# mechanics.net
KiCad netlist of a schematic drawn in Altium Designer
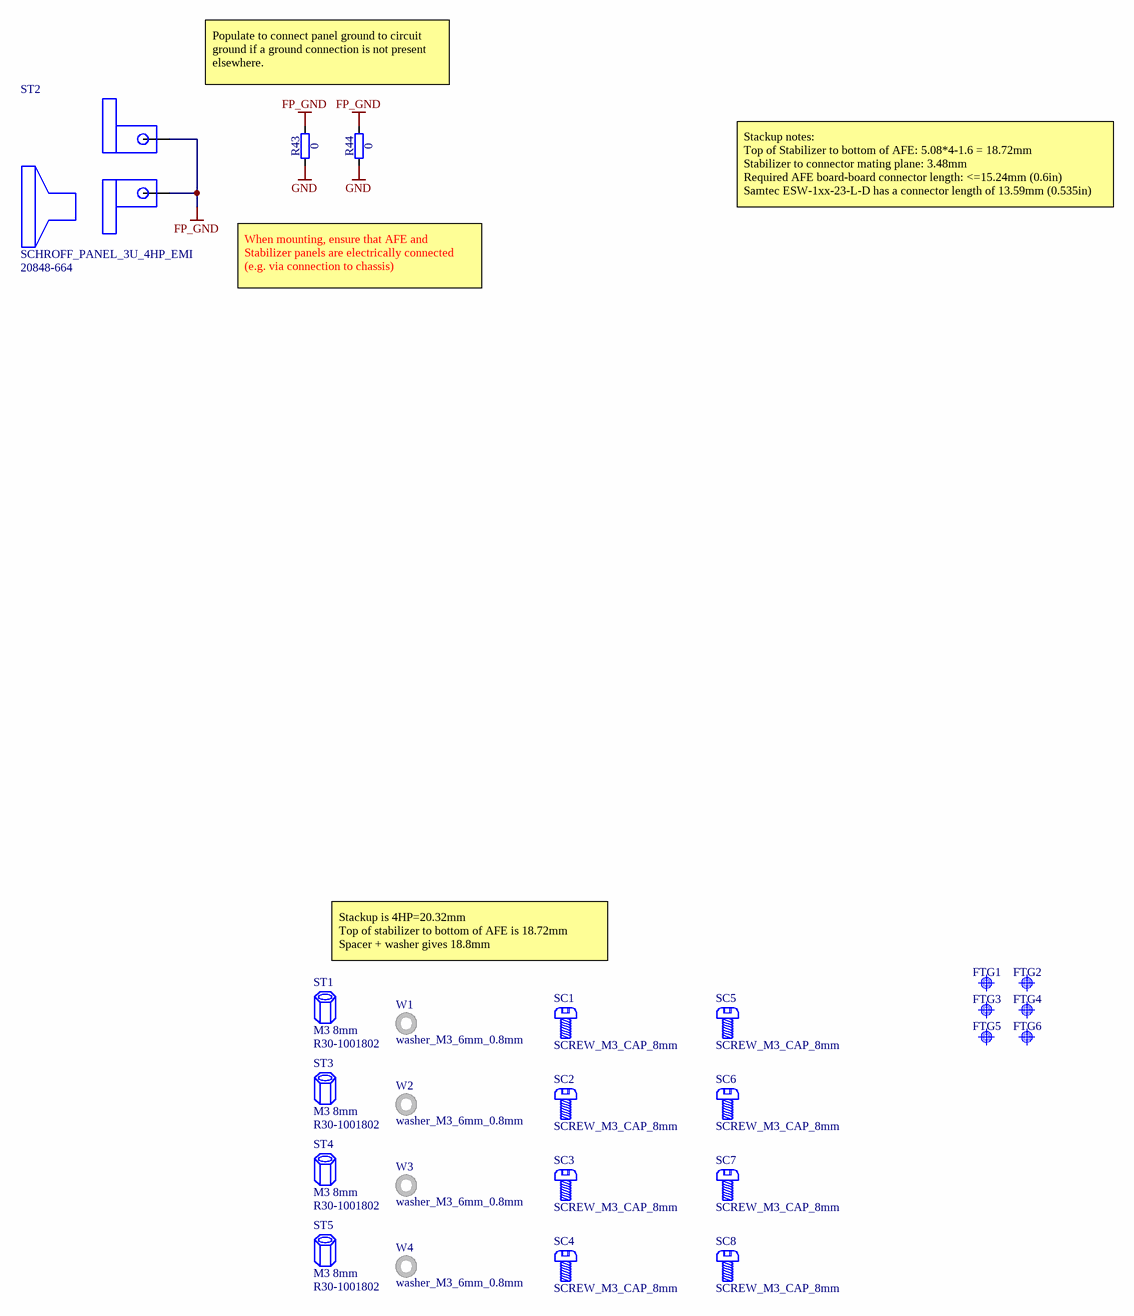
[diagram p0: mechanics.SchDoc]

(export (version "E")
  (design (tool "Eeschema 10.0.6"))
  (components
    (comp (ref "FTG1")
      (value "Use only in PCB")
      (footprint "FIDUCIAL_TOP_C100-200")
      (description "Fiducial Target")
      (fields (field (name "PART NUMBER") "FIDUCIAL_TARGET_C100-200") (field (name "AUTHOR") "CERN DEM JLC"))
      (libsource (lib "Eletro-mechanical") (part "Fiducial Target"))
    )
    (comp (ref "FTG2")
      (value "Use only in PCB")
      (footprint "FIDUCIAL_TOP_C100-200")
      (description "Fiducial Target")
      (fields (field (name "PART NUMBER") "FIDUCIAL_TARGET_C100-200") (field (name "AUTHOR") "CERN DEM JLC"))
      (libsource (lib "Eletro-mechanical") (part "Fiducial Target"))
    )
    (comp (ref "FTG3")
      (value "Use only in PCB")
      (footprint "FIDUCIAL_TOP_C100-200")
      (description "Fiducial Target")
      (fields (field (name "PART NUMBER") "FIDUCIAL_TARGET_C100-200") (field (name "AUTHOR") "CERN DEM JLC"))
      (libsource (lib "Eletro-mechanical") (part "Fiducial Target"))
    )
    (comp (ref "FTG4")
      (value "Use only in PCB")
      (footprint "FIDUCIAL_TOP_C100-200")
      (description "Fiducial Target")
      (fields (field (name "PART NUMBER") "FIDUCIAL_TARGET_C100-200") (field (name "AUTHOR") "CERN DEM JLC"))
      (libsource (lib "Eletro-mechanical") (part "Fiducial Target"))
    )
    (comp (ref "FTG5")
      (value "Use only in PCB")
      (footprint "FIDUCIAL_TOP_C100-200")
      (description "Fiducial Target")
      (fields (field (name "PART NUMBER") "FIDUCIAL_TARGET_C100-200") (field (name "AUTHOR") "CERN DEM JLC"))
      (libsource (lib "Eletro-mechanical") (part "Fiducial Target"))
    )
    (comp (ref "FTG6")
      (value "Use only in PCB")
      (footprint "FIDUCIAL_TOP_C100-200")
      (description "Fiducial Target")
      (fields (field (name "PART NUMBER") "FIDUCIAL_TARGET_C100-200") (field (name "AUTHOR") "CERN DEM JLC"))
      (libsource (lib "Eletro-mechanical") (part "Fiducial Target"))
    )
    (comp (ref "R43")
      (value "0")
      (footprint "RESC1608X55N")
      (description "Resistor")
      (fields
        (field (name "PART NUMBER") "R0603_0R_JUMPER")
        (field (name "MANUFACTURER") "GENERIC")
        (field (name "AUTHOR") "CERN DEM JLC")
      )
      (libsource (lib "Resistors") (part "Resistor"))
    )
    (comp (ref "R44")
      (value "0")
      (footprint "RESC1608X55N")
      (description "Resistor")
      (fields
        (field (name "PART NUMBER") "R0603_0R_JUMPER")
        (field (name "MANUFACTURER") "GENERIC")
        (field (name "AUTHOR") "CERN DEM JLC")
      )
      (libsource (lib "Resistors") (part "Resistor"))
    )
    (comp (ref "SC1")
      (value "SCREW_M3_CAP_8mm")
      (footprint "mechanical:SCREW_M3_CAP_8mm")
      (description "M3 x 8mm cap head screw")
      (fields
        (field (name "MANUFACTURER") "Accu Limited")
        (field (name "MANUFACTURER PART NUMBER") "SSCF-M3-8-12.9-Z")
      )
      (libsource (lib "mechanical") (part "SCREW_M3_CAP_8mm"))
    )
    (comp (ref "SC2")
      (value "SCREW_M3_CAP_8mm")
      (footprint "mechanical:SCREW_M3_CAP_8mm")
      (description "M3 x 8mm cap head screw")
      (fields
        (field (name "MANUFACTURER") "Accu Limited")
        (field (name "MANUFACTURER PART NUMBER") "SSCF-M3-8-12.9-Z")
      )
      (libsource (lib "mechanical") (part "SCREW_M3_CAP_8mm"))
    )
    (comp (ref "SC3")
      (value "SCREW_M3_CAP_8mm")
      (footprint "mechanical:SCREW_M3_CAP_8mm")
      (description "M3 x 8mm cap head screw")
      (fields
        (field (name "MANUFACTURER") "Accu Limited")
        (field (name "MANUFACTURER PART NUMBER") "SSCF-M3-8-12.9-Z")
      )
      (libsource (lib "mechanical") (part "SCREW_M3_CAP_8mm"))
    )
    (comp (ref "SC4")
      (value "SCREW_M3_CAP_8mm")
      (footprint "mechanical:SCREW_M3_CAP_8mm")
      (description "M3 x 8mm cap head screw")
      (fields
        (field (name "MANUFACTURER") "Accu Limited")
        (field (name "MANUFACTURER PART NUMBER") "SSCF-M3-8-12.9-Z")
      )
      (libsource (lib "mechanical") (part "SCREW_M3_CAP_8mm"))
    )
    (comp (ref "SC5")
      (value "SCREW_M3_CAP_8mm")
      (footprint "mechanical:SCREW_M3_CAP_8mm")
      (description "M3 x 8mm cap head screw")
      (fields
        (field (name "MANUFACTURER") "Accu Limited")
        (field (name "MANUFACTURER PART NUMBER") "SSCF-M3-8-12.9-Z")
      )
      (libsource (lib "mechanical") (part "SCREW_M3_CAP_8mm"))
    )
    (comp (ref "SC6")
      (value "SCREW_M3_CAP_8mm")
      (footprint "mechanical:SCREW_M3_CAP_8mm")
      (description "M3 x 8mm cap head screw")
      (fields
        (field (name "MANUFACTURER") "Accu Limited")
        (field (name "MANUFACTURER PART NUMBER") "SSCF-M3-8-12.9-Z")
      )
      (libsource (lib "mechanical") (part "SCREW_M3_CAP_8mm"))
    )
    (comp (ref "SC7")
      (value "SCREW_M3_CAP_8mm")
      (footprint "mechanical:SCREW_M3_CAP_8mm")
      (description "M3 x 8mm cap head screw")
      (fields
        (field (name "MANUFACTURER") "Accu Limited")
        (field (name "MANUFACTURER PART NUMBER") "SSCF-M3-8-12.9-Z")
      )
      (libsource (lib "mechanical") (part "SCREW_M3_CAP_8mm"))
    )
    (comp (ref "SC8")
      (value "SCREW_M3_CAP_8mm")
      (footprint "mechanical:SCREW_M3_CAP_8mm")
      (description "M3 x 8mm cap head screw")
      (fields
        (field (name "MANUFACTURER") "Accu Limited")
        (field (name "MANUFACTURER PART NUMBER") "SSCF-M3-8-12.9-Z")
      )
      (libsource (lib "mechanical") (part "SCREW_M3_CAP_8mm"))
    )
    (comp (ref "ST1")
      (value "M3 8mm")
      (footprint "mechanical:R30-1001802")
      (description "M3.0x18 standoff")
      (fields (field (name "MANUFACTURER") "Harwin") (field (name "MANUFACTURER PART NUMBER") "R30-1001802"))
      (libsource (lib "mechanical") (part "STANDOFF_HARWIN_R30_1001802"))
    )
    (comp (ref "ST2")
      (value "SCHROFF_PANEL_3U_4HP_EMI")
      (footprint "mechanical:SCHROFF_PANEL_3HP_4U")
      (description "Schroff 3HP 4U EUROCARD Panel with EMI gaskets kit")
      (fields (field (name "MANUFACTURER") "Schroff") (field (name "MANUFACTURER PART NUMBER") "20848-664"))
      (libsource (lib "mechanical") (part "SCHROFF_PANEL_3U_4HP_EMI"))
    )
    (comp (ref "ST3")
      (value "M3 8mm")
      (footprint "mechanical:R30-1001802")
      (description "M3.0x18 standoff")
      (fields (field (name "MANUFACTURER") "Harwin") (field (name "MANUFACTURER PART NUMBER") "R30-1001802"))
      (libsource (lib "mechanical") (part "STANDOFF_HARWIN_R30_1001802"))
    )
    (comp (ref "ST4")
      (value "M3 8mm")
      (footprint "mechanical:R30-1001802")
      (description "M3.0x18 standoff")
      (fields (field (name "MANUFACTURER") "Harwin") (field (name "MANUFACTURER PART NUMBER") "R30-1001802"))
      (libsource (lib "mechanical") (part "STANDOFF_HARWIN_R30_1001802"))
    )
    (comp (ref "ST5")
      (value "M3 8mm")
      (footprint "mechanical:R30-1001802")
      (description "M3.0x18 standoff")
      (fields (field (name "MANUFACTURER") "Harwin") (field (name "MANUFACTURER PART NUMBER") "R30-1001802"))
      (libsource (lib "mechanical") (part "STANDOFF_HARWIN_R30_1001802"))
    )
    (comp (ref "W1")
      (value "washer_M3_6mm_0.8mm")
      (footprint "mechanical:washer_M3_6mm_0.8mm")
      (description "M3 Washer:\r\nID: 3.2mm\r\nOD: 6mm\r\nThickness 0.8mm")
      (fields
        (field (name "MANUFACTURER") "Accu Limited")
        (field (name "MANUFACTURER PART NUMBER") "HAFZ-M3-A4")
      )
      (libsource (lib "mechanical") (part "washer_M3_6mm_0.8mm"))
    )
    (comp (ref "W2")
      (value "washer_M3_6mm_0.8mm")
      (footprint "mechanical:washer_M3_6mm_0.8mm")
      (description "M3 Washer:\r\nID: 3.2mm\r\nOD: 6mm\r\nThickness 0.8mm")
      (fields
        (field (name "MANUFACTURER") "Accu Limited")
        (field (name "MANUFACTURER PART NUMBER") "HAFZ-M3-A4")
      )
      (libsource (lib "mechanical") (part "washer_M3_6mm_0.8mm"))
    )
    (comp (ref "W3")
      (value "washer_M3_6mm_0.8mm")
      (footprint "mechanical:washer_M3_6mm_0.8mm")
      (description "M3 Washer:\r\nID: 3.2mm\r\nOD: 6mm\r\nThickness 0.8mm")
      (fields
        (field (name "MANUFACTURER") "Accu Limited")
        (field (name "MANUFACTURER PART NUMBER") "HAFZ-M3-A4")
      )
      (libsource (lib "mechanical") (part "washer_M3_6mm_0.8mm"))
    )
    (comp (ref "W4")
      (value "washer_M3_6mm_0.8mm")
      (footprint "mechanical:washer_M3_6mm_0.8mm")
      (description "M3 Washer:\r\nID: 3.2mm\r\nOD: 6mm\r\nThickness 0.8mm")
      (fields
        (field (name "MANUFACTURER") "Accu Limited")
        (field (name "MANUFACTURER PART NUMBER") "HAFZ-M3-A4")
      )
      (libsource (lib "mechanical") (part "washer_M3_6mm_0.8mm"))
    )
  )
  (nets
    (net (code "1") (name "FP_GND") (class "Default")
      (node (ref "R43") (pin "2") (pinfunction "2_2") (pintype "passive"))
      (node (ref "R44") (pin "2") (pinfunction "2_2") (pintype "passive"))
      (node (ref "ST2") (pin "0") (pinfunction "0_0") (pintype "passive"))
      (node (ref "ST2") (pin "1") (pinfunction "1_1") (pintype "passive"))
    )
    (net (code "2") (name "GND") (class "Default")
      (node (ref "R43") (pin "1") (pinfunction "1_1") (pintype "passive"))
      (node (ref "R44") (pin "1") (pinfunction "1_1") (pintype "passive"))
    )
  )
)
